# BrainA1-5March2015.net
KiCad netlist of a schematic drawn in EAGLE
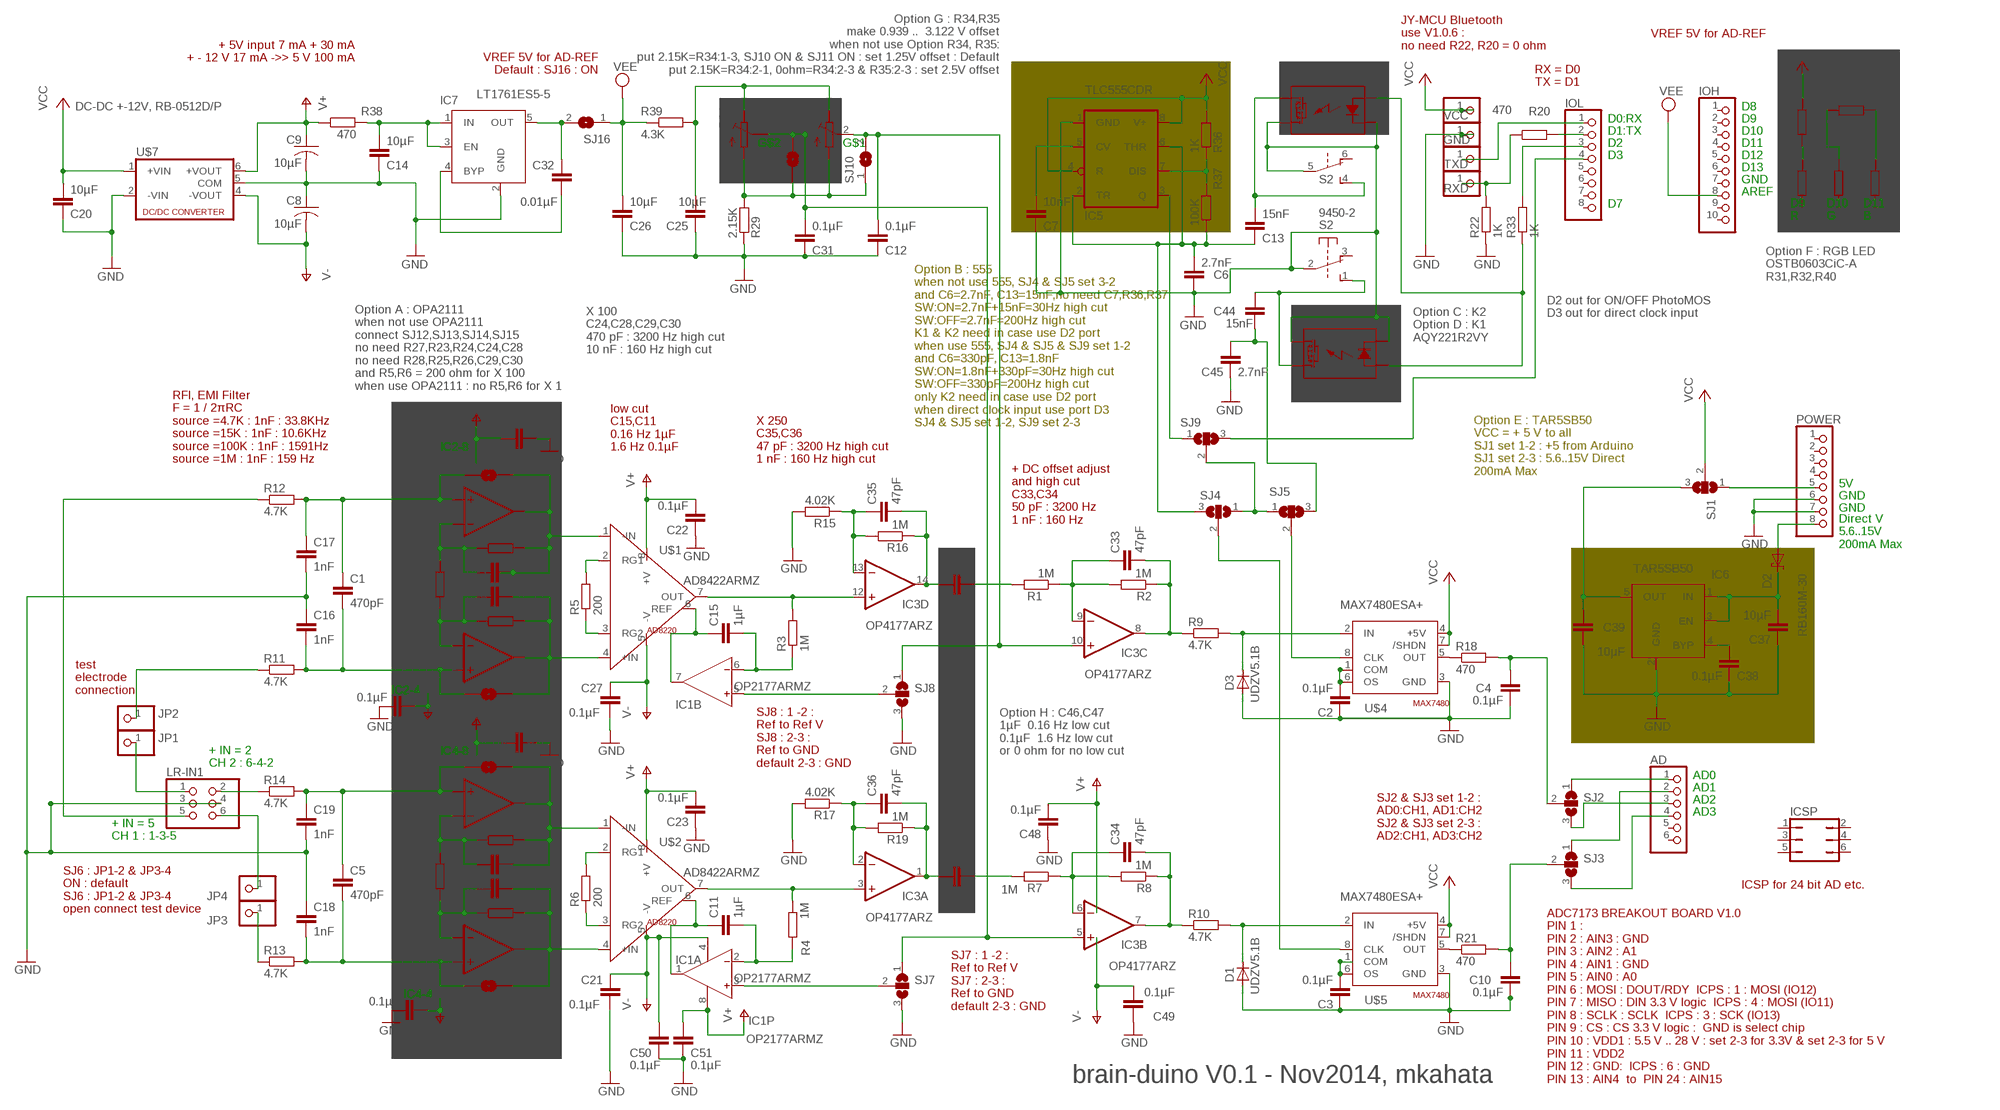
[diagram p0: schematic, sheet 1]

(export (version "E")
  (design (tool "Eeschema 10.0.6"))
  (components
    (comp (ref "AD")
      (value "PINHD-1X6")
      (footprint "eagle-import:1X06")
      (libsource (lib "eagle-import") (part "PINHD-1X6"))
    )
    (comp (ref "C1")
      (value "470pF")
      (footprint "eagle-import:C0805")
      (libsource (lib "eagle-import") (part "C-EUC0805"))
    )
    (comp (ref "C2")
      (value "0.1µF")
      (footprint "eagle-import:C0805")
      (libsource (lib "eagle-import") (part "C-EUC0805"))
    )
    (comp (ref "C3")
      (value "0.1µF")
      (footprint "eagle-import:C0805")
      (libsource (lib "eagle-import") (part "C-EUC0805"))
    )
    (comp (ref "C4")
      (value "0.1µF")
      (footprint "eagle-import:C0805")
      (libsource (lib "eagle-import") (part "C-EUC0805"))
    )
    (comp (ref "C5")
      (value "470pF")
      (footprint "eagle-import:C0805")
      (libsource (lib "eagle-import") (part "C-EUC0805"))
    )
    (comp (ref "C6")
      (value "2.7nF")
      (footprint "eagle-import:C0805")
      (libsource (lib "eagle-import") (part "C-EUC0805"))
    )
    (comp (ref "C7")
      (value "10nF")
      (footprint "eagle-import:C0805")
      (libsource (lib "eagle-import") (part "C-EUC0805"))
    )
    (comp (ref "C8")
      (value "10µF")
      (footprint "eagle-import:C0805")
      (libsource (lib "eagle-import") (part "C-USC0805"))
    )
    (comp (ref "C9")
      (value "10µF")
      (footprint "eagle-import:C0805")
      (libsource (lib "eagle-import") (part "C-USC0805"))
    )
    (comp (ref "C10")
      (value "0.1µF")
      (footprint "eagle-import:C0805")
      (libsource (lib "eagle-import") (part "C-EUC0805"))
    )
    (comp (ref "C11")
      (value "1µF")
      (footprint "eagle-import:C0805")
      (libsource (lib "eagle-import") (part "C-EUC0805"))
    )
    (comp (ref "C12")
      (value "0.1µF")
      (footprint "eagle-import:C0805")
      (libsource (lib "eagle-import") (part "C-EUC0805"))
    )
    (comp (ref "C13")
      (value "15nF")
      (footprint "eagle-import:C0805")
      (libsource (lib "eagle-import") (part "C-EUC0805"))
    )
    (comp (ref "C14")
      (value "10µF")
      (footprint "eagle-import:C0805")
      (libsource (lib "eagle-import") (part "C-EUC0805"))
    )
    (comp (ref "C15")
      (value "1µF")
      (footprint "eagle-import:C0805")
      (libsource (lib "eagle-import") (part "C-EUC0805"))
    )
    (comp (ref "C16")
      (value "1nF")
      (footprint "eagle-import:C0805")
      (libsource (lib "eagle-import") (part "C-EUC0805"))
    )
    (comp (ref "C17")
      (value "1nF")
      (footprint "eagle-import:C0805")
      (libsource (lib "eagle-import") (part "C-EUC0805"))
    )
    (comp (ref "C18")
      (value "1nF")
      (footprint "eagle-import:C0805")
      (libsource (lib "eagle-import") (part "C-EUC0805"))
    )
    (comp (ref "C19")
      (value "1nF")
      (footprint "eagle-import:C0805")
      (libsource (lib "eagle-import") (part "C-EUC0805"))
    )
    (comp (ref "C20")
      (value "10µF")
      (footprint "eagle-import:C0805")
      (libsource (lib "eagle-import") (part "C-EUC0805"))
    )
    (comp (ref "C21")
      (value "0.1µF")
      (footprint "eagle-import:C0805")
      (libsource (lib "eagle-import") (part "C-EUC0805"))
    )
    (comp (ref "C22")
      (value "0.1µF")
      (footprint "eagle-import:C0805")
      (libsource (lib "eagle-import") (part "C-EUC0805"))
    )
    (comp (ref "C23")
      (value "0.1µF")
      (footprint "eagle-import:C0805")
      (libsource (lib "eagle-import") (part "C-EUC0805"))
    )
    (comp (ref "C24")
      (value "470pF")
      (footprint "eagle-import:C0805")
      (libsource (lib "eagle-import") (part "C-EUC0805"))
    )
    (comp (ref "C25")
      (value "10µF")
      (footprint "eagle-import:C0805")
      (libsource (lib "eagle-import") (part "C-EUC0805"))
    )
    (comp (ref "C26")
      (value "10µF")
      (footprint "eagle-import:C0805")
      (libsource (lib "eagle-import") (part "C-EUC0805"))
    )
    (comp (ref "C27")
      (value "0.1µF")
      (footprint "eagle-import:C0805")
      (libsource (lib "eagle-import") (part "C-EUC0805"))
    )
    (comp (ref "C28")
      (value "470pF")
      (footprint "eagle-import:C0805")
      (libsource (lib "eagle-import") (part "C-EUC0805"))
    )
    (comp (ref "C29")
      (value "470pF")
      (footprint "eagle-import:C0805")
      (libsource (lib "eagle-import") (part "C-EUC0805"))
    )
    (comp (ref "C30")
      (value "470pF")
      (footprint "eagle-import:C0805")
      (libsource (lib "eagle-import") (part "C-EUC0805"))
    )
    (comp (ref "C31")
      (value "0.1µF")
      (footprint "eagle-import:C0805")
      (libsource (lib "eagle-import") (part "C-EUC0805"))
    )
    (comp (ref "C32")
      (value "0.01µF")
      (footprint "eagle-import:C0805")
      (libsource (lib "eagle-import") (part "C-EUC0805"))
    )
    (comp (ref "C33")
      (value "47pF")
      (footprint "eagle-import:C0805")
      (libsource (lib "eagle-import") (part "C-EUC0805"))
    )
    (comp (ref "C34")
      (value "47pF")
      (footprint "eagle-import:C0805")
      (libsource (lib "eagle-import") (part "C-EUC0805"))
    )
    (comp (ref "C35")
      (value "47pF")
      (footprint "eagle-import:C0805")
      (libsource (lib "eagle-import") (part "C-EUC0805"))
    )
    (comp (ref "C36")
      (value "47pF")
      (footprint "eagle-import:C0805")
      (libsource (lib "eagle-import") (part "C-EUC0805"))
    )
    (comp (ref "C37")
      (value "10µF")
      (footprint "eagle-import:C0805")
      (libsource (lib "eagle-import") (part "C-EUC0805"))
    )
    (comp (ref "C38")
      (value "0.1µF")
      (footprint "eagle-import:C0805")
      (libsource (lib "eagle-import") (part "C-EUC0805"))
    )
    (comp (ref "C39")
      (value "10µF")
      (footprint "eagle-import:C0805")
      (libsource (lib "eagle-import") (part "C-EUC0805"))
    )
    (comp (ref "C40")
      (value "0.1µF")
      (footprint "eagle-import:C0805")
      (libsource (lib "eagle-import") (part "C-EUC0805"))
    )
    (comp (ref "C41")
      (value "0.1µF")
      (footprint "eagle-import:C0805")
      (libsource (lib "eagle-import") (part "C-EUC0805"))
    )
    (comp (ref "C42")
      (value "0.1µF")
      (footprint "eagle-import:C0805")
      (libsource (lib "eagle-import") (part "C-EUC0805"))
    )
    (comp (ref "C43")
      (value "0.1µF")
      (footprint "eagle-import:C0805")
      (libsource (lib "eagle-import") (part "C-EUC0805"))
    )
    (comp (ref "C44")
      (value "15nF")
      (footprint "eagle-import:C0805")
      (libsource (lib "eagle-import") (part "C-EUC0805"))
    )
    (comp (ref "C45")
      (value "2.7nF")
      (footprint "eagle-import:C0805")
      (libsource (lib "eagle-import") (part "C-EUC0805"))
    )
    (comp (ref "C46")
      (value "1µF")
      (footprint "eagle-import:C0805")
      (libsource (lib "eagle-import") (part "C-EUC0805"))
    )
    (comp (ref "C47")
      (value "1µF")
      (footprint "eagle-import:C0805")
      (libsource (lib "eagle-import") (part "C-EUC0805"))
    )
    (comp (ref "C48")
      (value "0.1µF")
      (footprint "eagle-import:C0805")
      (libsource (lib "eagle-import") (part "C-EUC0805"))
    )
    (comp (ref "C49")
      (value "0.1µF")
      (footprint "eagle-import:C0805")
      (libsource (lib "eagle-import") (part "C-EUC0805"))
    )
    (comp (ref "C50")
      (value "0.1µF")
      (footprint "eagle-import:C0805")
      (libsource (lib "eagle-import") (part "C-EUC0805"))
    )
    (comp (ref "C51")
      (value "0.1µF")
      (footprint "eagle-import:C0805")
      (libsource (lib "eagle-import") (part "C-EUC0805"))
    )
    (comp (ref "D1")
      (value "UDZV5.1B")
      (footprint "eagle-import:SOD110-R")
      (libsource (lib "eagle-import") (part "DIODE-SOD110-R"))
    )
    (comp (ref "D2")
      (value "RB160M-30")
      (footprint "eagle-import:POWERDI323")
      (libsource (lib "eagle-import") (part "PD3S160"))
    )
    (comp (ref "D3")
      (value "UDZV5.1B")
      (footprint "eagle-import:SOD110-R")
      (libsource (lib "eagle-import") (part "DIODE-SOD110-R"))
    )
    (comp (ref "GND")
      (value "PINHD-1X1")
      (footprint "eagle-import:1X01")
      (libsource (lib "eagle-import") (part "PINHD-1X1"))
    )
    (comp (ref "IC1")
      (value "OP2177ARMZ")
      (footprint "eagle-import:MSOP08")
      (fields (field (name "MPN") "AD8656ARMZ"))
      (libsource (lib "eagle-import") (part "AD8656RM"))
    )
    (comp (ref "IC2")
      (value "OPA2111KP")
      (footprint "eagle-import:DIL08")
      (libsource (lib "eagle-import") (part "OPA2111P"))
    )
    (comp (ref "IC3")
      (value "OP4177ARZ")
      (footprint "eagle-import:SO14")
      (libsource (lib "eagle-import") (part "TL064D"))
    )
    (comp (ref "IC4")
      (value "OPA2111KP")
      (footprint "eagle-import:DIL08")
      (libsource (lib "eagle-import") (part "OPA2111P"))
    )
    (comp (ref "IC5")
      (value "TLC555CDR")
      (footprint "eagle-import:SO08")
      (libsource (lib "eagle-import") (part "555DLM"))
    )
    (comp (ref "IC6")
      (value "TAR5SB50")
      (footprint "eagle-import:SOT23-5")
      (libsource (lib "eagle-import") (part "MIC5219XX"))
    )
    (comp (ref "IC7")
      (value "LT1761ES5-5")
      (footprint "eagle-import:SOT23-5")
      (libsource (lib "eagle-import") (part "MIC5219XX"))
    )
    (comp (ref "ICSP")
      (value "JP3Q")
      (footprint "eagle-import:JP3Q")
      (libsource (lib "eagle-import") (part "JP3Q"))
    )
    (comp (ref "IOH")
      (value "PINHD-1X10")
      (footprint "eagle-import:1X10")
      (libsource (lib "eagle-import") (part "PINHD-1X10"))
    )
    (comp (ref "IOL")
      (value "PINHD-1X8")
      (footprint "eagle-import:1X08")
      (libsource (lib "eagle-import") (part "PINHD-1X8"))
    )
    (comp (ref "JP1")
      (value "PINHD-1X1")
      (footprint "eagle-import:1X01")
      (libsource (lib "eagle-import") (part "PINHD-1X1"))
    )
    (comp (ref "JP2")
      (value "PINHD-1X1")
      (footprint "eagle-import:1X01")
      (libsource (lib "eagle-import") (part "PINHD-1X1"))
    )
    (comp (ref "JP3")
      (value "PINHD-1X1")
      (footprint "eagle-import:1X01")
      (libsource (lib "eagle-import") (part "PINHD-1X1"))
    )
    (comp (ref "JP4")
      (value "PINHD-1X1")
      (footprint "eagle-import:1X01")
      (libsource (lib "eagle-import") (part "PINHD-1X1"))
    )
    (comp (ref "K1")
      (value "AQY221R2VY")
      (footprint "eagle-import:SSOP4")
      (fields (field (name "MF") "AROMAT/ MATSUSHITA") (field (name "MPN") "AQY221R2V"))
      (libsource (lib "eagle-import") (part "AQY2212VR"))
    )
    (comp (ref "K2")
      (value "AQY221R2VY")
      (footprint "eagle-import:SSOP4")
      (fields (field (name "MF") "AROMAT/ MATSUSHITA") (field (name "MPN") "AQY221R2V"))
      (libsource (lib "eagle-import") (part "AQY2212VR"))
    )
    (comp (ref "LR-IN1")
      (value "PINHD-2X3/90")
      (footprint "eagle-import:2X03_90")
      (libsource (lib "eagle-import") (part "PINHD-2X3/90"))
    )
    (comp (ref "POWER")
      (value "PINHD-1X8")
      (footprint "eagle-import:1X08")
      (libsource (lib "eagle-import") (part "PINHD-1X8"))
    )
    (comp (ref "R1")
      (value "1M")
      (footprint "eagle-import:R0805")
      (libsource (lib "eagle-import") (part "R-EU_R0805"))
    )
    (comp (ref "R2")
      (value "1M")
      (footprint "eagle-import:R0805")
      (libsource (lib "eagle-import") (part "R-EU_R0805"))
    )
    (comp (ref "R3")
      (value "1M")
      (footprint "eagle-import:R0805")
      (libsource (lib "eagle-import") (part "R-EU_R0805"))
    )
    (comp (ref "R4")
      (value "1M")
      (footprint "eagle-import:R0805")
      (libsource (lib "eagle-import") (part "R-EU_R0805"))
    )
    (comp (ref "R5")
      (value "200")
      (footprint "eagle-import:R0805")
      (libsource (lib "eagle-import") (part "R-EU_R0805"))
    )
    (comp (ref "R6")
      (value "200")
      (footprint "eagle-import:R0805")
      (libsource (lib "eagle-import") (part "R-EU_R0805"))
    )
    (comp (ref "R7")
      (value "1M")
      (footprint "eagle-import:R0805")
      (libsource (lib "eagle-import") (part "R-EU_R0805"))
    )
    (comp (ref "R8")
      (value "1M")
      (footprint "eagle-import:R0805")
      (libsource (lib "eagle-import") (part "R-EU_R0805"))
    )
    (comp (ref "R9")
      (value "4.7K")
      (footprint "eagle-import:R0805")
      (libsource (lib "eagle-import") (part "R-EU_R0805"))
    )
    (comp (ref "R10")
      (value "4.7K")
      (footprint "eagle-import:R0805")
      (libsource (lib "eagle-import") (part "R-EU_R0805"))
    )
    (comp (ref "R11")
      (value "4.7K")
      (footprint "eagle-import:R0805")
      (libsource (lib "eagle-import") (part "R-EU_R0805"))
    )
    (comp (ref "R12")
      (value "4.7K")
      (footprint "eagle-import:R0805")
      (libsource (lib "eagle-import") (part "R-EU_R0805"))
    )
    (comp (ref "R13")
      (value "4.7K")
      (footprint "eagle-import:R0805")
      (libsource (lib "eagle-import") (part "R-EU_R0805"))
    )
    (comp (ref "R14")
      (value "4.7K")
      (footprint "eagle-import:R0805")
      (libsource (lib "eagle-import") (part "R-EU_R0805"))
    )
    (comp (ref "R15")
      (value "4.02K")
      (footprint "eagle-import:R0805")
      (libsource (lib "eagle-import") (part "R-EU_R0805"))
    )
    (comp (ref "R16")
      (value "1M")
      (footprint "eagle-import:R0805")
      (libsource (lib "eagle-import") (part "R-EU_R0805"))
    )
    (comp (ref "R17")
      (value "4.02K")
      (footprint "eagle-import:R0805")
      (libsource (lib "eagle-import") (part "R-EU_R0805"))
    )
    (comp (ref "R18")
      (value "470")
      (footprint "eagle-import:R0805")
      (libsource (lib "eagle-import") (part "R-EU_R0805"))
    )
    (comp (ref "R19")
      (value "1M")
      (footprint "eagle-import:R0805")
      (libsource (lib "eagle-import") (part "R-EU_R0805"))
    )
    (comp (ref "R20")
      (value "470")
      (footprint "eagle-import:R0805")
      (libsource (lib "eagle-import") (part "R-EU_R0805"))
    )
    (comp (ref "R21")
      (value "470")
      (footprint "eagle-import:R0805")
      (libsource (lib "eagle-import") (part "R-EU_R0805"))
    )
    (comp (ref "R22")
      (value "1K")
      (footprint "eagle-import:R0805")
      (libsource (lib "eagle-import") (part "R-EU_R0805"))
    )
    (comp (ref "R23")
      (value "100K")
      (footprint "eagle-import:R0805")
      (libsource (lib "eagle-import") (part "R-EU_R0805"))
    )
    (comp (ref "R24")
      (value "100K")
      (footprint "eagle-import:R0805")
      (libsource (lib "eagle-import") (part "R-EU_R0805"))
    )
    (comp (ref "R25")
      (value "100K")
      (footprint "eagle-import:R0805")
      (libsource (lib "eagle-import") (part "R-EU_R0805"))
    )
    (comp (ref "R26")
      (value "100K")
      (footprint "eagle-import:R0805")
      (libsource (lib "eagle-import") (part "R-EU_R0805"))
    )
    (comp (ref "R27")
      (value "2K")
      (footprint "eagle-import:R0805")
      (libsource (lib "eagle-import") (part "R-EU_R0805"))
    )
    (comp (ref "R28")
      (value "2K")
      (footprint "eagle-import:R0805")
      (libsource (lib "eagle-import") (part "R-EU_R0805"))
    )
    (comp (ref "R29")
      (value "2.15K")
      (footprint "eagle-import:R0805")
      (libsource (lib "eagle-import") (part "R-EU_R0805"))
    )
    (comp (ref "R30")
      (value "LED")
      (footprint "eagle-import:R0402")
      (libsource (lib "eagle-import") (part "R-EU_R0402"))
    )
    (comp (ref "R31")
      (value "1K")
      (footprint "eagle-import:R0402")
      (libsource (lib "eagle-import") (part "R-EU_R0402"))
    )
    (comp (ref "R32")
      (value "1K")
      (footprint "eagle-import:R0402")
      (libsource (lib "eagle-import") (part "R-EU_R0402"))
    )
    (comp (ref "R33")
      (value "1K")
      (footprint "eagle-import:R0805")
      (libsource (lib "eagle-import") (part "R-EU_R0805"))
    )
    (comp (ref "R34")
      (value "10K")
      (footprint "eagle-import:RTRIM5X")
      (libsource (lib "eagle-import") (part "R-TRIMM5X"))
    )
    (comp (ref "R35")
      (value "10K")
      (footprint "eagle-import:RTRIM5X")
      (libsource (lib "eagle-import") (part "R-TRIMM5X"))
    )
    (comp (ref "R36")
      (value "1K")
      (footprint "eagle-import:R0805")
      (libsource (lib "eagle-import") (part "R-EU_R0805"))
    )
    (comp (ref "R37")
      (value "100K")
      (footprint "eagle-import:R0805")
      (libsource (lib "eagle-import") (part "R-EU_R0805"))
    )
    (comp (ref "R38")
      (value "470")
      (footprint "eagle-import:R0805")
      (libsource (lib "eagle-import") (part "R-EU_R0805"))
    )
    (comp (ref "R39")
      (value "4.3K")
      (footprint "eagle-import:R0805")
      (libsource (lib "eagle-import") (part "R-EU_R0805"))
    )
    (comp (ref "R40")
      (value "1K")
      (footprint "eagle-import:R0402")
      (libsource (lib "eagle-import") (part "R-EU_R0402"))
    )
    (comp (ref "R41")
      (value "LED")
      (footprint "eagle-import:R0402")
      (libsource (lib "eagle-import") (part "R-EU_R0402"))
    )
    (comp (ref "RXD")
      (value "PINHD-1X1")
      (footprint "eagle-import:1X01")
      (libsource (lib "eagle-import") (part "PINHD-1X1"))
    )
    (comp (ref "S2")
      (value "9450-2")
      (footprint "eagle-import:9450-2")
      (libsource (lib "eagle-import") (part "9450-2"))
    )
    (comp (ref "SJ1")
      (value "SJ2W")
      (footprint "eagle-import:SJ_2")
      (libsource (lib "eagle-import") (part "SJ2W"))
    )
    (comp (ref "SJ2")
      (value "SJ2W")
      (footprint "eagle-import:SJ_2")
      (libsource (lib "eagle-import") (part "SJ2W"))
    )
    (comp (ref "SJ3")
      (value "SJ2W")
      (footprint "eagle-import:SJ_2")
      (libsource (lib "eagle-import") (part "SJ2W"))
    )
    (comp (ref "SJ4")
      (value "SJ2W")
      (footprint "eagle-import:SJ_2")
      (libsource (lib "eagle-import") (part "SJ2W"))
    )
    (comp (ref "SJ5")
      (value "SJ2W")
      (footprint "eagle-import:SJ_2")
      (libsource (lib "eagle-import") (part "SJ2W"))
    )
    (comp (ref "SJ7")
      (value "SJ2W")
      (footprint "eagle-import:SJ_2")
      (libsource (lib "eagle-import") (part "SJ2W"))
    )
    (comp (ref "SJ8")
      (value "SJ2W")
      (footprint "eagle-import:SJ_2")
      (libsource (lib "eagle-import") (part "SJ2W"))
    )
    (comp (ref "SJ9")
      (value "SJ2W")
      (footprint "eagle-import:SJ_2")
      (libsource (lib "eagle-import") (part "SJ2W"))
    )
    (comp (ref "SJ10")
      (value "SJ")
      (footprint "eagle-import:SJ")
      (libsource (lib "eagle-import") (part "SJ"))
    )
    (comp (ref "SJ11")
      (value "SJ")
      (footprint "eagle-import:SJ")
      (libsource (lib "eagle-import") (part "SJ"))
    )
    (comp (ref "SJ12")
      (value "SJ")
      (footprint "eagle-import:SJ")
      (libsource (lib "eagle-import") (part "SJ"))
    )
    (comp (ref "SJ13")
      (value "SJ")
      (footprint "eagle-import:SJ")
      (libsource (lib "eagle-import") (part "SJ"))
    )
    (comp (ref "SJ14")
      (value "SJ")
      (footprint "eagle-import:SJ")
      (libsource (lib "eagle-import") (part "SJ"))
    )
    (comp (ref "SJ15")
      (value "SJ")
      (footprint "eagle-import:SJ")
      (libsource (lib "eagle-import") (part "SJ"))
    )
    (comp (ref "SJ16")
      (value "SJ")
      (footprint "eagle-import:SJ")
      (libsource (lib "eagle-import") (part "SJ"))
    )
    (comp (ref "TXD")
      (value "PINHD-1X1")
      (footprint "eagle-import:1X01")
      (libsource (lib "eagle-import") (part "PINHD-1X1"))
    )
    (comp (ref "U$1")
      (value "AD8422ARMZ")
      (footprint "eagle-import:AD8220")
      (libsource (lib "eagle-import") (part "AD8220"))
    )
    (comp (ref "U$2")
      (value "AD8422ARMZ")
      (footprint "eagle-import:AD8220")
      (libsource (lib "eagle-import") (part "AD8220"))
    )
    (comp (ref "U$4")
      (value "MAX7480ESA+")
      (footprint "eagle-import:MAX7480")
      (libsource (lib "eagle-import") (part "MAX7480"))
    )
    (comp (ref "U$5")
      (value "MAX7480ESA+")
      (footprint "eagle-import:MAX7480")
      (libsource (lib "eagle-import") (part "MAX7480"))
    )
    (comp (ref "U$7")
      (value "DC-DC +-12V, RB-0512D/P")
      (footprint "eagle-import:RB-0515D")
      (libsource (lib "eagle-import") (part "RB-0515D"))
    )
    (comp (ref "VCC")
      (value "PINHD-1X1")
      (footprint "eagle-import:1X01")
      (libsource (lib "eagle-import") (part "PINHD-1X1"))
    )
  )
  (nets
    (net (code "1") (name "GND") (class "Default")
      (node (ref "C10") (pin "1") (pinfunction "1_1") (pintype "passive"))
      (node (ref "C12") (pin "1") (pinfunction "1_1") (pintype "passive"))
      (node (ref "C14") (pin "1") (pinfunction "1_1") (pintype "passive"))
      (node (ref "C16") (pin "1") (pinfunction "1_1") (pintype "passive"))
      (node (ref "C17") (pin "2") (pinfunction "2_2") (pintype "passive"))
      (node (ref "C18") (pin "1") (pinfunction "1_1") (pintype "passive"))
      (node (ref "C19") (pin "2") (pinfunction "2_2") (pintype "passive"))
      (node (ref "C2") (pin "1") (pinfunction "1_1") (pintype "passive"))
      (node (ref "C20") (pin "1") (pinfunction "1_1") (pintype "passive"))
      (node (ref "C21") (pin "2") (pinfunction "2_2") (pintype "passive"))
      (node (ref "C22") (pin "1") (pinfunction "1_1") (pintype "passive"))
      (node (ref "C23") (pin "1") (pinfunction "1_1") (pintype "passive"))
      (node (ref "C25") (pin "1") (pinfunction "1_1") (pintype "passive"))
      (node (ref "C26") (pin "1") (pinfunction "1_1") (pintype "passive"))
      (node (ref "C27") (pin "2") (pinfunction "2_2") (pintype "passive"))
      (node (ref "C3") (pin "1") (pinfunction "1_1") (pintype "passive"))
      (node (ref "C31") (pin "1") (pinfunction "1_1") (pintype "passive"))
      (node (ref "C37") (pin "1") (pinfunction "1_1") (pintype "passive"))
      (node (ref "C38") (pin "1") (pinfunction "1_1") (pintype "passive"))
      (node (ref "C39") (pin "1") (pinfunction "1_1") (pintype "passive"))
      (node (ref "C4") (pin "1") (pinfunction "1_1") (pintype "passive"))
      (node (ref "C40") (pin "1") (pinfunction "1_1") (pintype "passive"))
      (node (ref "C41") (pin "2") (pinfunction "2_2") (pintype "passive"))
      (node (ref "C42") (pin "2") (pinfunction "2_2") (pintype "passive"))
      (node (ref "C43") (pin "2") (pinfunction "2_2") (pintype "passive"))
      (node (ref "C45") (pin "1") (pinfunction "1_1") (pintype "passive"))
      (node (ref "C48") (pin "1") (pinfunction "1_1") (pintype "passive"))
      (node (ref "C49") (pin "1") (pinfunction "1_1") (pintype "passive"))
      (node (ref "C50") (pin "2") (pinfunction "2_2") (pintype "passive"))
      (node (ref "C51") (pin "2") (pinfunction "2_2") (pintype "passive"))
      (node (ref "C6") (pin "1") (pinfunction "1_1") (pintype "passive"))
      (node (ref "C7") (pin "1") (pinfunction "1_1") (pintype "passive"))
      (node (ref "C8") (pin "1") (pinfunction "1_1") (pintype "passive"))
      (node (ref "C9") (pin "2") (pinfunction "2_2") (pintype "passive"))
      (node (ref "D1") (pin "A") (pinfunction "A_A") (pintype "passive"))
      (node (ref "D3") (pin "A") (pinfunction "A_A") (pintype "passive"))
      (node (ref "GND") (pin "1") (pinfunction "1_1") (pintype "passive"))
      (node (ref "IC5") (pin "1") (pinfunction "GND_1") (pintype "power_in"))
      (node (ref "IC6") (pin "2") (pinfunction "GND_2") (pintype "power_in"))
      (node (ref "IC7") (pin "2") (pinfunction "GND_2") (pintype "power_in"))
      (node (ref "K1") (pin "2") (pinfunction "K_2") (pintype "passive"))
      (node (ref "K1") (pin "3") (pinfunction "DS2_3") (pintype "passive"))
      (node (ref "K2") (pin "2") (pinfunction "K_2") (pintype "passive"))
      (node (ref "K2") (pin "3") (pinfunction "DS2_3") (pintype "passive"))
      (node (ref "LR-IN1") (pin "3") (pinfunction "3_3") (pintype "passive"))
      (node (ref "LR-IN1") (pin "4") (pinfunction "4_4") (pintype "passive"))
      (node (ref "POWER") (pin "6") (pinfunction "6_6") (pintype "passive"))
      (node (ref "POWER") (pin "7") (pinfunction "7_7") (pintype "passive"))
      (node (ref "R15") (pin "2") (pinfunction "2_2") (pintype "passive"))
      (node (ref "R17") (pin "2") (pinfunction "2_2") (pintype "passive"))
      (node (ref "R22") (pin "1") (pinfunction "1_1") (pintype "passive"))
      (node (ref "R29") (pin "1") (pinfunction "1_1") (pintype "passive"))
      (node (ref "S2") (pin "2") (pinfunction "P_2") (pintype "passive"))
      (node (ref "S2") (pin "5") (pinfunction "P_5") (pintype "passive"))
      (node (ref "SJ7") (pin "3") (pinfunction "3_3") (pintype "passive"))
      (node (ref "SJ8") (pin "3") (pinfunction "3_3") (pintype "passive"))
      (node (ref "U$4") (pin "3") (pinfunction "GND_3") (pintype "power_in"))
      (node (ref "U$5") (pin "3") (pinfunction "GND_3") (pintype "power_in"))
      (node (ref "U$7") (pin "2") (pinfunction "-VIN_2") (pintype "passive"))
      (node (ref "U$7") (pin "5") (pinfunction "COM_5") (pintype "passive"))
    )
    (net (code "2") (name "Net-(AD-Pad1)") (class "Default")
      (node (ref "AD") (pin "1") (pinfunction "1_1") (pintype "passive"))
      (node (ref "SJ2") (pin "1") (pinfunction "1_1") (pintype "passive"))
    )
    (net (code "3") (name "Net-(AD-Pad2)") (class "Default")
      (node (ref "AD") (pin "2") (pinfunction "2_2") (pintype "passive"))
      (node (ref "SJ3") (pin "1") (pinfunction "1_1") (pintype "passive"))
    )
    (net (code "4") (name "Net-(AD-Pad3)") (class "Default")
      (node (ref "AD") (pin "3") (pinfunction "3_3") (pintype "passive"))
      (node (ref "SJ2") (pin "3") (pinfunction "3_3") (pintype "passive"))
    )
    (net (code "5") (name "Net-(AD-Pad4)") (class "Default")
      (node (ref "AD") (pin "4") (pinfunction "4_4") (pintype "passive"))
      (node (ref "SJ3") (pin "3") (pinfunction "3_3") (pintype "passive"))
    )
    (net (code "6") (name "Net-(C4-Pad2)") (class "Default")
      (node (ref "C4") (pin "2") (pinfunction "2_2") (pintype "passive"))
      (node (ref "R18") (pin "2") (pinfunction "2_2") (pintype "passive"))
      (node (ref "SJ2") (pin "2") (pinfunction "2_2") (pintype "passive"))
    )
    (net (code "7") (name "Net-(C10-Pad2)") (class "Default")
      (node (ref "C10") (pin "2") (pinfunction "2_2") (pintype "passive"))
      (node (ref "R21") (pin "2") (pinfunction "2_2") (pintype "passive"))
      (node (ref "SJ3") (pin "2") (pinfunction "2_2") (pintype "passive"))
    )
    (net (code "8") (name "Net-(C44-Pad1)") (class "Default")
      (node (ref "C44") (pin "1") (pinfunction "1_1") (pintype "passive"))
      (node (ref "C45") (pin "2") (pinfunction "2_2") (pintype "passive"))
      (node (ref "SJ5") (pin "3") (pinfunction "3_3") (pintype "passive"))
    )
    (net (code "9") (name "Net-(C46-Pad2)") (class "Default")
      (node (ref "C46") (pin "2") (pinfunction "2_2") (pintype "passive"))
      (node (ref "R1") (pin "2") (pinfunction "2_2") (pintype "passive"))
    )
    (net (code "10") (name "Net-(C47-Pad2)") (class "Default")
      (node (ref "C47") (pin "2") (pinfunction "2_2") (pintype "passive"))
      (node (ref "R7") (pin "2") (pinfunction "2_2") (pintype "passive"))
    )
    (net (code "11") (name "Net-(D2-PadA)") (class "Default")
      (node (ref "D2") (pin "A") (pinfunction "A_A") (pintype "passive"))
      (node (ref "POWER") (pin "8") (pinfunction "8_8") (pintype "passive"))
    )
    (net (code "12") (name "Net-(IC1A-IN+)") (class "Default")
      (node (ref "IC1") (pin "3") (pinfunction "IN+_3") (pintype "input"))
      (node (ref "SJ7") (pin "2") (pinfunction "2_2") (pintype "passive"))
    )
    (net (code "13") (name "Net-(IC1A-IN-)") (class "Default")
      (node (ref "C11") (pin "2") (pinfunction "2_2") (pintype "passive"))
      (node (ref "IC1") (pin "2") (pinfunction "IN-_2") (pintype "input"))
      (node (ref "R4") (pin "1") (pinfunction "1_1") (pintype "passive"))
    )
    (net (code "14") (name "Net-(IC1A-OUT)") (class "Default")
      (node (ref "C11") (pin "1") (pinfunction "1_1") (pintype "passive"))
      (node (ref "IC1") (pin "1") (pinfunction "OUT_1") (pintype "output"))
      (node (ref "U$2") (pin "6") (pinfunction "REF_6") (pintype "input"))
    )
    (net (code "15") (name "Net-(IC1B-IN+)") (class "Default")
      (node (ref "IC1") (pin "5") (pinfunction "IN+_5") (pintype "input"))
      (node (ref "SJ8") (pin "2") (pinfunction "2_2") (pintype "passive"))
    )
    (net (code "16") (name "Net-(IC1B-IN-)") (class "Default")
      (node (ref "C15") (pin "2") (pinfunction "2_2") (pintype "passive"))
      (node (ref "IC1") (pin "6") (pinfunction "IN-_6") (pintype "input"))
      (node (ref "R3") (pin "1") (pinfunction "1_1") (pintype "passive"))
    )
    (net (code "17") (name "Net-(IC1B-OUT)") (class "Default")
      (node (ref "C15") (pin "1") (pinfunction "1_1") (pintype "passive"))
      (node (ref "IC1") (pin "7") (pinfunction "OUT_7") (pintype "output"))
      (node (ref "U$1") (pin "6") (pinfunction "REF_6") (pintype "input"))
    )
    (net (code "18") (name "Net-(IC2A-+IN)") (class "Default")
      (node (ref "C1") (pin "1") (pinfunction "1_1") (pintype "passive"))
      (node (ref "C17") (pin "1") (pinfunction "1_1") (pintype "passive"))
      (node (ref "IC2") (pin "3") (pinfunction "+IN_3") (pintype "input"))
      (node (ref "R12") (pin "2") (pinfunction "2_2") (pintype "passive"))
      (node (ref "SJ12") (pin "2") (pinfunction "2_2") (pintype "passive"))
    )
    (net (code "19") (name "Net-(IC2A--IN)") (class "Default")
      (node (ref "C24") (pin "1") (pinfunction "1_1") (pintype "passive"))
      (node (ref "IC2") (pin "2") (pinfunction "-IN_2") (pintype "input"))
      (node (ref "R23") (pin "1") (pinfunction "1_1") (pintype "passive"))
      (node (ref "R27") (pin "2") (pinfunction "2_2") (pintype "passive"))
    )
    (net (code "20") (name "Net-(IC2A-OUT)") (class "Default")
      (node (ref "C24") (pin "2") (pinfunction "2_2") (pintype "passive"))
      (node (ref "IC2") (pin "1") (pinfunction "OUT_1") (pintype "output"))
      (node (ref "R23") (pin "2") (pinfunction "2_2") (pintype "passive"))
      (node (ref "SJ12") (pin "1") (pinfunction "1_1") (pintype "passive"))
      (node (ref "U$1") (pin "1") (pinfunction "-IN_1") (pintype "input"))
    )
    (net (code "21") (name "Net-(IC2B-+IN)") (class "Default")
      (node (ref "C1") (pin "2") (pinfunction "2_2") (pintype "passive"))
      (node (ref "C16") (pin "2") (pinfunction "2_2") (pintype "passive"))
      (node (ref "IC2") (pin "5") (pinfunction "+IN_5") (pintype "input"))
      (node (ref "R11") (pin "2") (pinfunction "2_2") (pintype "passive"))
      (node (ref "SJ13") (pin "2") (pinfunction "2_2") (pintype "passive"))
    )
    (net (code "22") (name "Net-(IC2B--IN)") (class "Default")
      (node (ref "C28") (pin "1") (pinfunction "1_1") (pintype "passive"))
      (node (ref "IC2") (pin "6") (pinfunction "-IN_6") (pintype "input"))
      (node (ref "R24") (pin "1") (pinfunction "1_1") (pintype "passive"))
      (node (ref "R27") (pin "1") (pinfunction "1_1") (pintype "passive"))
    )
    (net (code "23") (name "Net-(IC2B-OUT)") (class "Default")
      (node (ref "C28") (pin "2") (pinfunction "2_2") (pintype "passive"))
      (node (ref "IC2") (pin "7") (pinfunction "OUT_7") (pintype "output"))
      (node (ref "R24") (pin "2") (pinfunction "2_2") (pintype "passive"))
      (node (ref "SJ13") (pin "1") (pinfunction "1_1") (pintype "passive"))
      (node (ref "U$1") (pin "4") (pinfunction "+IN_4") (pintype "passive"))
    )
    (net (code "24") (name "Net-(IC3A-+IN)") (class "Default")
      (node (ref "IC3") (pin "3") (pinfunction "+IN_3") (pintype "input"))
      (node (ref "R4") (pin "2") (pinfunction "2_2") (pintype "passive"))
      (node (ref "U$2") (pin "7") (pinfunction "OUT_7") (pintype "input"))
    )
    (net (code "25") (name "Net-(IC3A--IN)") (class "Default")
      (node (ref "C36") (pin "1") (pinfunction "1_1") (pintype "passive"))
      (node (ref "IC3") (pin "2") (pinfunction "-IN_2") (pintype "input"))
      (node (ref "R17") (pin "1") (pinfunction "1_1") (pintype "passive"))
      (node (ref "R19") (pin "2") (pinfunction "2_2") (pintype "passive"))
    )
    (net (code "26") (name "Net-(IC3A-OUT)") (class "Default")
      (node (ref "C36") (pin "2") (pinfunction "2_2") (pintype "passive"))
      (node (ref "C47") (pin "1") (pinfunction "1_1") (pintype "passive"))
      (node (ref "IC3") (pin "1") (pinfunction "OUT_1") (pintype "output"))
      (node (ref "R19") (pin "1") (pinfunction "1_1") (pintype "passive"))
    )
    (net (code "27") (name "Net-(IC3B-+IN)") (class "Default")
      (node (ref "C31") (pin "2") (pinfunction "2_2") (pintype "passive"))
      (node (ref "IC3") (pin "5") (pinfunction "+IN_5") (pintype "input"))
      (node (ref "R34") (pin "2") (pinfunction "S_2") (pintype "passive"))
      (node (ref "SJ11") (pin "2") (pinfunction "2_2") (pintype "passive"))
      (node (ref "SJ7") (pin "1") (pinfunction "1_1") (pintype "passive"))
    )
    (net (code "28") (name "Net-(IC3B--IN)") (class "Default")
      (node (ref "C34") (pin "1") (pinfunction "1_1") (pintype "passive"))
      (node (ref "IC3") (pin "6") (pinfunction "-IN_6") (pintype "input"))
      (node (ref "R7") (pin "1") (pinfunction "1_1") (pintype "passive"))
      (node (ref "R8") (pin "2") (pinfunction "2_2") (pintype "passive"))
    )
    (net (code "29") (name "Net-(IC3B-OUT)") (class "Default")
      (node (ref "C34") (pin "2") (pinfunction "2_2") (pintype "passive"))
      (node (ref "IC3") (pin "7") (pinfunction "OUT_7") (pintype "output"))
      (node (ref "R10") (pin "1") (pinfunction "1_1") (pintype "passive"))
      (node (ref "R8") (pin "1") (pinfunction "1_1") (pintype "passive"))
    )
    (net (code "30") (name "Net-(IC3C-+IN)") (class "Default")
      (node (ref "C12") (pin "2") (pinfunction "2_2") (pintype "passive"))
      (node (ref "IC3") (pin "10") (pinfunction "+IN_10") (pintype "input"))
      (node (ref "R35") (pin "2") (pinfunction "S_2") (pintype "passive"))
      (node (ref "SJ10") (pin "2") (pinfunction "2_2") (pintype "passive"))
      (node (ref "SJ8") (pin "1") (pinfunction "1_1") (pintype "passive"))
    )
    (net (code "31") (name "Net-(IC3C--IN)") (class "Default")
      (node (ref "C33") (pin "1") (pinfunction "1_1") (pintype "passive"))
      (node (ref "IC3") (pin "9") (pinfunction "-IN_9") (pintype "input"))
      (node (ref "R1") (pin "1") (pinfunction "1_1") (pintype "passive"))
      (node (ref "R2") (pin "2") (pinfunction "2_2") (pintype "passive"))
    )
    (net (code "32") (name "Net-(IC3C-OUT)") (class "Default")
      (node (ref "C33") (pin "2") (pinfunction "2_2") (pintype "passive"))
      (node (ref "IC3") (pin "8") (pinfunction "OUT_8") (pintype "output"))
      (node (ref "R2") (pin "1") (pinfunction "1_1") (pintype "passive"))
      (node (ref "R9") (pin "1") (pinfunction "1_1") (pintype "passive"))
    )
    (net (code "33") (name "Net-(IC3D-+IN)") (class "Default")
      (node (ref "IC3") (pin "12") (pinfunction "+IN_12") (pintype "input"))
      (node (ref "R3") (pin "2") (pinfunction "2_2") (pintype "passive"))
      (node (ref "U$1") (pin "7") (pinfunction "OUT_7") (pintype "input"))
    )
    (net (code "34") (name "Net-(IC3D--IN)") (class "Default")
      (node (ref "C35") (pin "1") (pinfunction "1_1") (pintype "passive"))
      (node (ref "IC3") (pin "13") (pinfunction "-IN_13") (pintype "input"))
      (node (ref "R15") (pin "1") (pinfunction "1_1") (pintype "passive"))
      (node (ref "R16") (pin "2") (pinfunction "2_2") (pintype "passive"))
    )
    (net (code "35") (name "Net-(IC3D-OUT)") (class "Default")
      (node (ref "C35") (pin "2") (pinfunction "2_2") (pintype "passive"))
      (node (ref "C46") (pin "1") (pinfunction "1_1") (pintype "passive"))
      (node (ref "IC3") (pin "14") (pinfunction "OUT_14") (pintype "output"))
      (node (ref "R16") (pin "1") (pinfunction "1_1") (pintype "passive"))
    )
    (net (code "36") (name "Net-(IC4A-+IN)") (class "Default")
      (node (ref "C19") (pin "1") (pinfunction "1_1") (pintype "passive"))
      (node (ref "C5") (pin "1") (pinfunction "1_1") (pintype "passive"))
      (node (ref "IC4") (pin "3") (pinfunction "+IN_3") (pintype "input"))
      (node (ref "R14") (pin "2") (pinfunction "2_2") (pintype "passive"))
      (node (ref "SJ14") (pin "2") (pinfunction "2_2") (pintype "passive"))
    )
    (net (code "37") (name "Net-(IC4A--IN)") (class "Default")
      (node (ref "C29") (pin "1") (pinfunction "1_1") (pintype "passive"))
      (node (ref "IC4") (pin "2") (pinfunction "-IN_2") (pintype "input"))
      (node (ref "R25") (pin "1") (pinfunction "1_1") (pintype "passive"))
      (node (ref "R28") (pin "2") (pinfunction "2_2") (pintype "passive"))
    )
    (net (code "38") (name "Net-(IC4A-OUT)") (class "Default")
      (node (ref "C29") (pin "2") (pinfunction "2_2") (pintype "passive"))
      (node (ref "IC4") (pin "1") (pinfunction "OUT_1") (pintype "output"))
      (node (ref "R25") (pin "2") (pinfunction "2_2") (pintype "passive"))
      (node (ref "SJ14") (pin "1") (pinfunction "1_1") (pintype "passive"))
      (node (ref "U$2") (pin "1") (pinfunction "-IN_1") (pintype "input"))
    )
    (net (code "39") (name "Net-(IC4B-+IN)") (class "Default")
      (node (ref "C18") (pin "2") (pinfunction "2_2") (pintype "passive"))
      (node (ref "C5") (pin "2") (pinfunction "2_2") (pintype "passive"))
      (node (ref "IC4") (pin "5") (pinfunction "+IN_5") (pintype "input"))
      (node (ref "R13") (pin "2") (pinfunction "2_2") (pintype "passive"))
      (node (ref "SJ15") (pin "2") (pinfunction "2_2") (pintype "passive"))
    )
    (net (code "40") (name "Net-(IC4B--IN)") (class "Default")
      (node (ref "C30") (pin "1") (pinfunction "1_1") (pintype "passive"))
      (node (ref "IC4") (pin "6") (pinfunction "-IN_6") (pintype "input"))
      (node (ref "R26") (pin "1") (pinfunction "1_1") (pintype "passive"))
      (node (ref "R28") (pin "1") (pinfunction "1_1") (pintype "passive"))
    )
    (net (code "41") (name "Net-(IC4B-OUT)") (class "Default")
      (node (ref "C30") (pin "2") (pinfunction "2_2") (pintype "passive"))
      (node (ref "IC4") (pin "7") (pinfunction "OUT_7") (pintype "output"))
      (node (ref "R26") (pin "2") (pinfunction "2_2") (pintype "passive"))
      (node (ref "SJ15") (pin "1") (pinfunction "1_1") (pintype "passive"))
      (node (ref "U$2") (pin "4") (pinfunction "+IN_4") (pintype "passive"))
    )
    (net (code "42") (name "Net-(IC5-CV)") (class "Default")
      (node (ref "C7") (pin "2") (pinfunction "2_2") (pintype "passive"))
      (node (ref "IC5") (pin "5") (pinfunction "CV_5") (pintype "input"))
    )
    (net (code "43") (name "Net-(IC5-DIS)") (class "Default")
      (node (ref "IC5") (pin "7") (pinfunction "DIS_7") (pintype "input"))
      (node (ref "R36") (pin "1") (pinfunction "1_1") (pintype "passive"))
      (node (ref "R37") (pin "2") (pinfunction "2_2") (pintype "passive"))
    )
    (net (code "44") (name "Net-(IC5-Q)") (class "Default")
      (node (ref "IC5") (pin "3") (pinfunction "Q_3") (pintype "output"))
      (node (ref "SJ9") (pin "1") (pinfunction "1_1") (pintype "passive"))
    )
    (net (code "45") (name "Net-(IC5-THR)") (class "Default")
      (node (ref "C13") (pin "1") (pinfunction "1_1") (pintype "passive"))
      (node (ref "C6") (pin "2") (pinfunction "2_2") (pintype "passive"))
      (node (ref "IC5") (pin "2") (pinfunction "TR_2") (pintype "input"))
      (node (ref "IC5") (pin "6") (pinfunction "THR_6") (pintype "input"))
      (node (ref "R37") (pin "1") (pinfunction "1_1") (pintype "passive"))
      (node (ref "SJ4") (pin "3") (pinfunction "3_3") (pintype "passive"))
    )
    (net (code "46") (name "Net-(IC6-BYP)") (class "Default")
      (node (ref "C38") (pin "2") (pinfunction "2_2") (pintype "passive"))
      (node (ref "IC6") (pin "4") (pinfunction "BYP_4") (pintype "passive"))
    )
    (net (code "47") (name "Net-(IC6-EN)") (class "Default")
      (node (ref "C37") (pin "2") (pinfunction "2_2") (pintype "passive"))
      (node (ref "D2") (pin "C") (pinfunction "C_C") (pintype "passive"))
      (node (ref "IC6") (pin "1") (pinfunction "IN_1") (pintype "input"))
      (node (ref "IC6") (pin "3") (pinfunction "EN_3") (pintype "input"))
    )
    (net (code "48") (name "Net-(IC6-OUT)") (class "Default")
      (node (ref "C39") (pin "2") (pinfunction "2_2") (pintype "passive"))
      (node (ref "IC6") (pin "5") (pinfunction "OUT_5") (pintype "output"))
      (node (ref "SJ1") (pin "3") (pinfunction "3_3") (pintype "passive"))
    )
    (net (code "49") (name "Net-(IC7-BYP)") (class "Default")
      (node (ref "C32") (pin "1") (pinfunction "1_1") (pintype "passive"))
      (node (ref "IC7") (pin "4") (pinfunction "BYP_4") (pintype "passive"))
    )
    (net (code "50") (name "Net-(IC7-EN)") (class "Default")
      (node (ref "C14") (pin "2") (pinfunction "2_2") (pintype "passive"))
      (node (ref "IC7") (pin "1") (pinfunction "IN_1") (pintype "input"))
      (node (ref "IC7") (pin "3") (pinfunction "EN_3") (pintype "input"))
      (node (ref "R38") (pin "2") (pinfunction "2_2") (pintype "passive"))
    )
    (net (code "51") (name "Net-(IC7-OUT)") (class "Default")
      (node (ref "C32") (pin "2") (pinfunction "2_2") (pintype "passive"))
      (node (ref "IC7") (pin "5") (pinfunction "OUT_5") (pintype "output"))
      (node (ref "SJ16") (pin "2") (pinfunction "2_2") (pintype "passive"))
    )
    (net (code "52") (name "Net-(IOL-Pad1)") (class "Default")
      (node (ref "IOL") (pin "1") (pinfunction "1_1") (pintype "passive"))
      (node (ref "TXD") (pin "1") (pinfunction "1_1") (pintype "passive"))
    )
    (net (code "53") (name "Net-(IOL-Pad2)") (class "Default")
      (node (ref "IOL") (pin "2") (pinfunction "2_2") (pintype "passive"))
      (node (ref "R20") (pin "2") (pinfunction "2_2") (pintype "passive"))
    )
    (net (code "54") (name "Net-(IOL-Pad3)") (class "Default")
      (node (ref "IOL") (pin "3") (pinfunction "3_3") (pintype "passive"))
      (node (ref "R33") (pin "2") (pinfunction "2_2") (pintype "passive"))
    )
    (net (code "55") (name "Net-(IOL-Pad4)") (class "Default")
      (node (ref "IOL") (pin "4") (pinfunction "4_4") (pintype "passive"))
      (node (ref "SJ9") (pin "3") (pinfunction "3_3") (pintype "passive"))
    )
    (net (code "56") (name "Net-(JP1-Pad1)") (class "Default")
      (node (ref "JP1") (pin "1") (pinfunction "1_1") (pintype "passive"))
      (node (ref "LR-IN1") (pin "1") (pinfunction "1_1") (pintype "passive"))
    )
    (net (code "57") (name "Net-(JP2-Pad1)") (class "Default")
      (node (ref "JP2") (pin "1") (pinfunction "1_1") (pintype "passive"))
      (node (ref "R11") (pin "1") (pinfunction "1_1") (pintype "passive"))
    )
    (net (code "58") (name "Net-(JP3-Pad1)") (class "Default")
      (node (ref "JP3") (pin "1") (pinfunction "1_1") (pintype "passive"))
      (node (ref "R13") (pin "1") (pinfunction "1_1") (pintype "passive"))
    )
    (net (code "59") (name "Net-(JP4-Pad1)") (class "Default")
      (node (ref "JP4") (pin "1") (pinfunction "1_1") (pintype "passive"))
      (node (ref "LR-IN1") (pin "6") (pinfunction "6_6") (pintype "passive"))
    )
    (net (code "60") (name "Net-(K1-A)") (class "Default")
      (node (ref "K1") (pin "1") (pinfunction "A_1") (pintype "passive"))
      (node (ref "K2") (pin "1") (pinfunction "A_1") (pintype "passive"))
      (node (ref "R33") (pin "1") (pinfunction "1_1") (pintype "passive"))
    )
    (net (code "61") (name "Net-(K1-DS1)") (class "Default")
      (node (ref "C44") (pin "2") (pinfunction "2_2") (pintype "passive"))
      (node (ref "K1") (pin "4") (pinfunction "DS1_4") (pintype "passive"))
      (node (ref "S2") (pin "1") (pinfunction "S_1") (pintype "passive"))
    )
    (net (code "62") (name "Net-(K2-DS1)") (class "Default")
      (node (ref "C13") (pin "2") (pinfunction "2_2") (pintype "passive"))
      (node (ref "K2") (pin "4") (pinfunction "DS1_4") (pintype "passive"))
      (node (ref "S2") (pin "4") (pinfunction "S_4") (pintype "passive"))
    )
    (net (code "63") (name "Net-(LR-IN1-Pad2)") (class "Default")
      (node (ref "LR-IN1") (pin "2") (pinfunction "2_2") (pintype "passive"))
      (node (ref "R14") (pin "1") (pinfunction "1_1") (pintype "passive"))
    )
    (net (code "64") (name "Net-(LR-IN1-Pad5)") (class "Default")
      (node (ref "LR-IN1") (pin "5") (pinfunction "5_5") (pintype "passive"))
      (node (ref "R12") (pin "1") (pinfunction "1_1") (pintype "passive"))
    )
    (net (code "65") (name "Net-(POWER-Pad5)") (class "Default")
      (node (ref "POWER") (pin "5") (pinfunction "5_5") (pintype "passive"))
      (node (ref "SJ1") (pin "1") (pinfunction "1_1") (pintype "passive"))
    )
    (net (code "66") (name "Net-(R20-Pad1)") (class "Default")
      (node (ref "R20") (pin "1") (pinfunction "1_1") (pintype "passive"))
      (node (ref "R22") (pin "2") (pinfunction "2_2") (pintype "passive"))
      (node (ref "RXD") (pin "1") (pinfunction "1_1") (pintype "passive"))
    )
    (net (code "67") (name "Net-(R30-Pad1)") (class "Default")
      (node (ref "R30") (pin "1") (pinfunction "1_1") (pintype "passive"))
      (node (ref "R40") (pin "2") (pinfunction "2_2") (pintype "passive"))
    )
    (net (code "68") (name "Net-(R30-Pad2)") (class "Default")
      (node (ref "R30") (pin "2") (pinfunction "2_2") (pintype "passive"))
      (node (ref "R32") (pin "2") (pinfunction "2_2") (pintype "passive"))
    )
    (net (code "69") (name "Net-(R31-Pad2)") (class "Default")
      (node (ref "R31") (pin "2") (pinfunction "2_2") (pintype "passive"))
      (node (ref "R41") (pin "1") (pinfunction "1_1") (pintype "passive"))
    )
    (net (code "70") (name "Net-(R34-A)") (class "Default")
      (node (ref "C25") (pin "2") (pinfunction "2_2") (pintype "passive"))
      (node (ref "R34") (pin "3") (pinfunction "A_3") (pintype "passive"))
      (node (ref "R35") (pin "3") (pinfunction "A_3") (pintype "passive"))
      (node (ref "R39") (pin "2") (pinfunction "2_2") (pintype "passive"))
    )
    (net (code "71") (name "Net-(R34-E)") (class "Default")
      (node (ref "R29") (pin "2") (pinfunction "2_2") (pintype "passive"))
      (node (ref "R34") (pin "1") (pinfunction "E_1") (pintype "passive"))
      (node (ref "R35") (pin "1") (pinfunction "E_1") (pintype "passive"))
      (node (ref "SJ10") (pin "1") (pinfunction "1_1") (pintype "passive"))
      (node (ref "SJ11") (pin "1") (pinfunction "1_1") (pintype "passive"))
    )
    (net (code "72") (name "Net-(SJ4-Pad1)") (class "Default")
      (node (ref "SJ4") (pin "1") (pinfunction "1_1") (pintype "passive"))
      (node (ref "SJ5") (pin "1") (pinfunction "1_1") (pintype "passive"))
      (node (ref "SJ9") (pin "2") (pinfunction "2_2") (pintype "passive"))
    )
    (net (code "73") (name "Net-(U$1-RG1)") (class "Default")
      (node (ref "R5") (pin "2") (pinfunction "2_2") (pintype "passive"))
      (node (ref "U$1") (pin "2") (pinfunction "RG1_2") (pintype "input"))
    )
    (net (code "74") (name "Net-(U$1-RG2)") (class "Default")
      (node (ref "R5") (pin "1") (pinfunction "1_1") (pintype "passive"))
      (node (ref "U$1") (pin "3") (pinfunction "RG2_3") (pintype "input"))
    )
    (net (code "75") (name "Net-(U$2-RG1)") (class "Default")
      (node (ref "R6") (pin "2") (pinfunction "2_2") (pintype "passive"))
      (node (ref "U$2") (pin "2") (pinfunction "RG1_2") (pintype "input"))
    )
    (net (code "76") (name "Net-(U$2-RG2)") (class "Default")
      (node (ref "R6") (pin "1") (pinfunction "1_1") (pintype "passive"))
      (node (ref "U$2") (pin "3") (pinfunction "RG2_3") (pintype "input"))
    )
    (net (code "77") (name "Net-(U$4-CLK)") (class "Default")
      (node (ref "SJ5") (pin "2") (pinfunction "2_2") (pintype "passive"))
      (node (ref "U$4") (pin "8") (pinfunction "CLK_8") (pintype "input"))
    )
    (net (code "78") (name "Net-(U$4-COM)") (class "Default")
      (node (ref "C2") (pin "2") (pinfunction "2_2") (pintype "passive"))
      (node (ref "U$4") (pin "1") (pinfunction "COM_1") (pintype "input"))
      (node (ref "U$4") (pin "6") (pinfunction "OS_6") (pintype "passive"))
    )
    (net (code "79") (name "Net-(U$4-IN)") (class "Default")
      (node (ref "D3") (pin "C") (pinfunction "C_C") (pintype "passive"))
      (node (ref "R9") (pin "2") (pinfunction "2_2") (pintype "passive"))
      (node (ref "U$4") (pin "2") (pinfunction "IN_2") (pintype "input"))
    )
    (net (code "80") (name "Net-(U$4-OUT)") (class "Default")
      (node (ref "R18") (pin "1") (pinfunction "1_1") (pintype "passive"))
      (node (ref "U$4") (pin "5") (pinfunction "OUT_5") (pintype "input"))
    )
    (net (code "81") (name "Net-(U$5-CLK)") (class "Default")
      (node (ref "SJ4") (pin "2") (pinfunction "2_2") (pintype "passive"))
      (node (ref "U$5") (pin "8") (pinfunction "CLK_8") (pintype "input"))
    )
    (net (code "82") (name "Net-(U$5-COM)") (class "Default")
      (node (ref "C3") (pin "2") (pinfunction "2_2") (pintype "passive"))
      (node (ref "U$5") (pin "1") (pinfunction "COM_1") (pintype "input"))
      (node (ref "U$5") (pin "6") (pinfunction "OS_6") (pintype "passive"))
    )
    (net (code "83") (name "Net-(U$5-IN)") (class "Default")
      (node (ref "D1") (pin "C") (pinfunction "C_C") (pintype "passive"))
      (node (ref "R10") (pin "2") (pinfunction "2_2") (pintype "passive"))
      (node (ref "U$5") (pin "2") (pinfunction "IN_2") (pintype "input"))
    )
    (net (code "84") (name "Net-(U$5-OUT)") (class "Default")
      (node (ref "R21") (pin "1") (pinfunction "1_1") (pintype "passive"))
      (node (ref "U$5") (pin "5") (pinfunction "OUT_5") (pintype "input"))
    )
    (net (code "85") (name "V+") (class "Default")
      (node (ref "C22") (pin "2") (pinfunction "2_2") (pintype "passive"))
      (node (ref "C23") (pin "2") (pinfunction "2_2") (pintype "passive"))
      (node (ref "C40") (pin "2") (pinfunction "2_2") (pintype "passive"))
      (node (ref "C42") (pin "1") (pinfunction "1_1") (pintype "passive"))
      (node (ref "C48") (pin "2") (pinfunction "2_2") (pintype "passive"))
      (node (ref "C51") (pin "1") (pinfunction "1_1") (pintype "passive"))
      (node (ref "C9") (pin "1") (pinfunction "1_1") (pintype "passive"))
      (node (ref "IC1") (pin "8") (pinfunction "V+_8") (pintype "power_in"))
      (node (ref "R38") (pin "1") (pinfunction "1_1") (pintype "passive"))
      (node (ref "U$1") (pin "8") (pinfunction "+V_8") (pintype "power_in"))
      (node (ref "U$2") (pin "8") (pinfunction "+V_8") (pintype "power_in"))
      (node (ref "U$7") (pin "6") (pinfunction "+VOUT_6") (pintype "passive"))
    )
    (net (code "86") (name "V-") (class "Default")
      (node (ref "C21") (pin "1") (pinfunction "1_1") (pintype "passive"))
      (node (ref "C27") (pin "1") (pinfunction "1_1") (pintype "passive"))
      (node (ref "C41") (pin "1") (pinfunction "1_1") (pintype "passive"))
      (node (ref "C43") (pin "1") (pinfunction "1_1") (pintype "passive"))
      (node (ref "C49") (pin "2") (pinfunction "2_2") (pintype "passive"))
      (node (ref "C50") (pin "1") (pinfunction "1_1") (pintype "passive"))
      (node (ref "C8") (pin "2") (pinfunction "2_2") (pintype "passive"))
      (node (ref "IC1") (pin "4") (pinfunction "V-_4") (pintype "power_in"))
      (node (ref "U$1") (pin "5") (pinfunction "-V_5") (pintype "power_in"))
      (node (ref "U$2") (pin "5") (pinfunction "-V_5") (pintype "power_in"))
      (node (ref "U$7") (pin "4") (pinfunction "-VOUT_4") (pintype "passive"))
    )
    (net (code "87") (name "VCC") (class "Default")
      (node (ref "C20") (pin "2") (pinfunction "2_2") (pintype "passive"))
      (node (ref "IC5") (pin "4") (pinfunction "R_4") (pintype "input"))
      (node (ref "IC5") (pin "8") (pinfunction "V+_8") (pintype "power_in"))
      (node (ref "R36") (pin "2") (pinfunction "2_2") (pintype "passive"))
      (node (ref "R41") (pin "2") (pinfunction "2_2") (pintype "passive"))
      (node (ref "SJ1") (pin "2") (pinfunction "2_2") (pintype "passive"))
      (node (ref "U$4") (pin "4") (pinfunction "+5V_4") (pintype "power_in"))
      (node (ref "U$4") (pin "7") (pinfunction "/SHDN_7") (pintype "input"))
      (node (ref "U$5") (pin "4") (pinfunction "+5V_4") (pintype "power_in"))
      (node (ref "U$5") (pin "7") (pinfunction "/SHDN_7") (pintype "input"))
      (node (ref "U$7") (pin "1") (pinfunction "+VIN_1") (pintype "passive"))
      (node (ref "VCC") (pin "1") (pinfunction "1_1") (pintype "passive"))
    )
    (net (code "88") (name "VEE") (class "Default")
      (node (ref "C26") (pin "2") (pinfunction "2_2") (pintype "passive"))
      (node (ref "IOH") (pin "8") (pinfunction "8_8") (pintype "passive"))
      (node (ref "R39") (pin "1") (pinfunction "1_1") (pintype "passive"))
      (node (ref "SJ16") (pin "1") (pinfunction "1_1") (pintype "passive"))
    )
    (net (code "89") (name "unconnected-(AD-Pad5)") (class "Default")
      (node (ref "AD") (pin "5") (pinfunction "5_5") (pintype "passive"))
    )
    (net (code "90") (name "unconnected-(AD-Pad6)") (class "Default")
      (node (ref "AD") (pin "6") (pinfunction "6_6") (pintype "passive"))
    )
    (net (code "91") (name "unconnected-(ICSP-Pad1)") (class "Default")
      (node (ref "ICSP") (pin "1") (pinfunction "1_1") (pintype "passive"))
    )
    (net (code "92") (name "unconnected-(ICSP-Pad2)") (class "Default")
      (node (ref "ICSP") (pin "2") (pinfunction "2_2") (pintype "passive"))
    )
    (net (code "93") (name "unconnected-(ICSP-Pad3)") (class "Default")
      (node (ref "ICSP") (pin "3") (pinfunction "3_3") (pintype "passive"))
    )
    (net (code "94") (name "unconnected-(ICSP-Pad4)") (class "Default")
      (node (ref "ICSP") (pin "4") (pinfunction "4_4") (pintype "passive"))
    )
    (net (code "95") (name "unconnected-(ICSP-Pad5)") (class "Default")
      (node (ref "ICSP") (pin "5") (pinfunction "5_5") (pintype "passive"))
    )
    (net (code "96") (name "unconnected-(ICSP-Pad6)") (class "Default")
      (node (ref "ICSP") (pin "6") (pinfunction "6_6") (pintype "passive"))
    )
    (net (code "97") (name "unconnected-(IOH-Pad1)") (class "Default")
      (node (ref "IOH") (pin "1") (pinfunction "1_1") (pintype "passive"))
    )
    (net (code "98") (name "unconnected-(IOH-Pad2)") (class "Default")
      (node (ref "IOH") (pin "2") (pinfunction "2_2") (pintype "passive"))
    )
    (net (code "99") (name "unconnected-(IOH-Pad3)") (class "Default")
      (node (ref "IOH") (pin "3") (pinfunction "3_3") (pintype "passive"))
    )
    (net (code "100") (name "unconnected-(IOH-Pad4)") (class "Default")
      (node (ref "IOH") (pin "4") (pinfunction "4_4") (pintype "passive"))
    )
    (net (code "101") (name "unconnected-(IOH-Pad5)") (class "Default")
      (node (ref "IOH") (pin "5") (pinfunction "5_5") (pintype "passive"))
    )
    (net (code "102") (name "unconnected-(IOH-Pad6)") (class "Default")
      (node (ref "IOH") (pin "6") (pinfunction "6_6") (pintype "passive"))
    )
    (net (code "103") (name "unconnected-(IOH-Pad7)") (class "Default")
      (node (ref "IOH") (pin "7") (pinfunction "7_7") (pintype "passive"))
    )
    (net (code "104") (name "unconnected-(IOH-Pad9)") (class "Default")
      (node (ref "IOH") (pin "9") (pinfunction "9_9") (pintype "passive"))
    )
    (net (code "105") (name "unconnected-(IOH-Pad10)") (class "Default")
      (node (ref "IOH") (pin "10") (pinfunction "10_10") (pintype "passive"))
    )
    (net (code "106") (name "unconnected-(IOL-Pad5)") (class "Default")
      (node (ref "IOL") (pin "5") (pinfunction "5_5") (pintype "passive"))
    )
    (net (code "107") (name "unconnected-(IOL-Pad6)") (class "Default")
      (node (ref "IOL") (pin "6") (pinfunction "6_6") (pintype "passive"))
    )
    (net (code "108") (name "unconnected-(IOL-Pad7)") (class "Default")
      (node (ref "IOL") (pin "7") (pinfunction "7_7") (pintype "passive"))
    )
    (net (code "109") (name "unconnected-(IOL-Pad8)") (class "Default")
      (node (ref "IOL") (pin "8") (pinfunction "8_8") (pintype "passive"))
    )
    (net (code "110") (name "unconnected-(POWER-Pad1)") (class "Default")
      (node (ref "POWER") (pin "1") (pinfunction "1_1") (pintype "passive"))
    )
    (net (code "111") (name "unconnected-(POWER-Pad2)") (class "Default")
      (node (ref "POWER") (pin "2") (pinfunction "2_2") (pintype "passive"))
    )
    (net (code "112") (name "unconnected-(POWER-Pad3)") (class "Default")
      (node (ref "POWER") (pin "3") (pinfunction "3_3") (pintype "passive"))
    )
    (net (code "113") (name "unconnected-(POWER-Pad4)") (class "Default")
      (node (ref "POWER") (pin "4") (pinfunction "4_4") (pintype "passive"))
    )
    (net (code "114") (name "unconnected-(R31-Pad1)") (class "Default")
      (node (ref "R31") (pin "1") (pinfunction "1_1") (pintype "passive"))
    )
    (net (code "115") (name "unconnected-(R32-Pad1)") (class "Default")
      (node (ref "R32") (pin "1") (pinfunction "1_1") (pintype "passive"))
    )
    (net (code "116") (name "unconnected-(R40-Pad1)") (class "Default")
      (node (ref "R40") (pin "1") (pinfunction "1_1") (pintype "passive"))
    )
    (net (code "117") (name "unconnected-(S2A-O-Pad3)") (class "Default")
      (node (ref "S2") (pin "3") (pinfunction "O_3") (pintype "passive"))
    )
    (net (code "118") (name "unconnected-(S2B-O-Pad6)") (class "Default")
      (node (ref "S2") (pin "6") (pinfunction "O_6") (pintype "passive"))
    )
  )
)
